# RetinaAdapterBoard.net
KiCad netlist of a schematic drawn in EAGLE
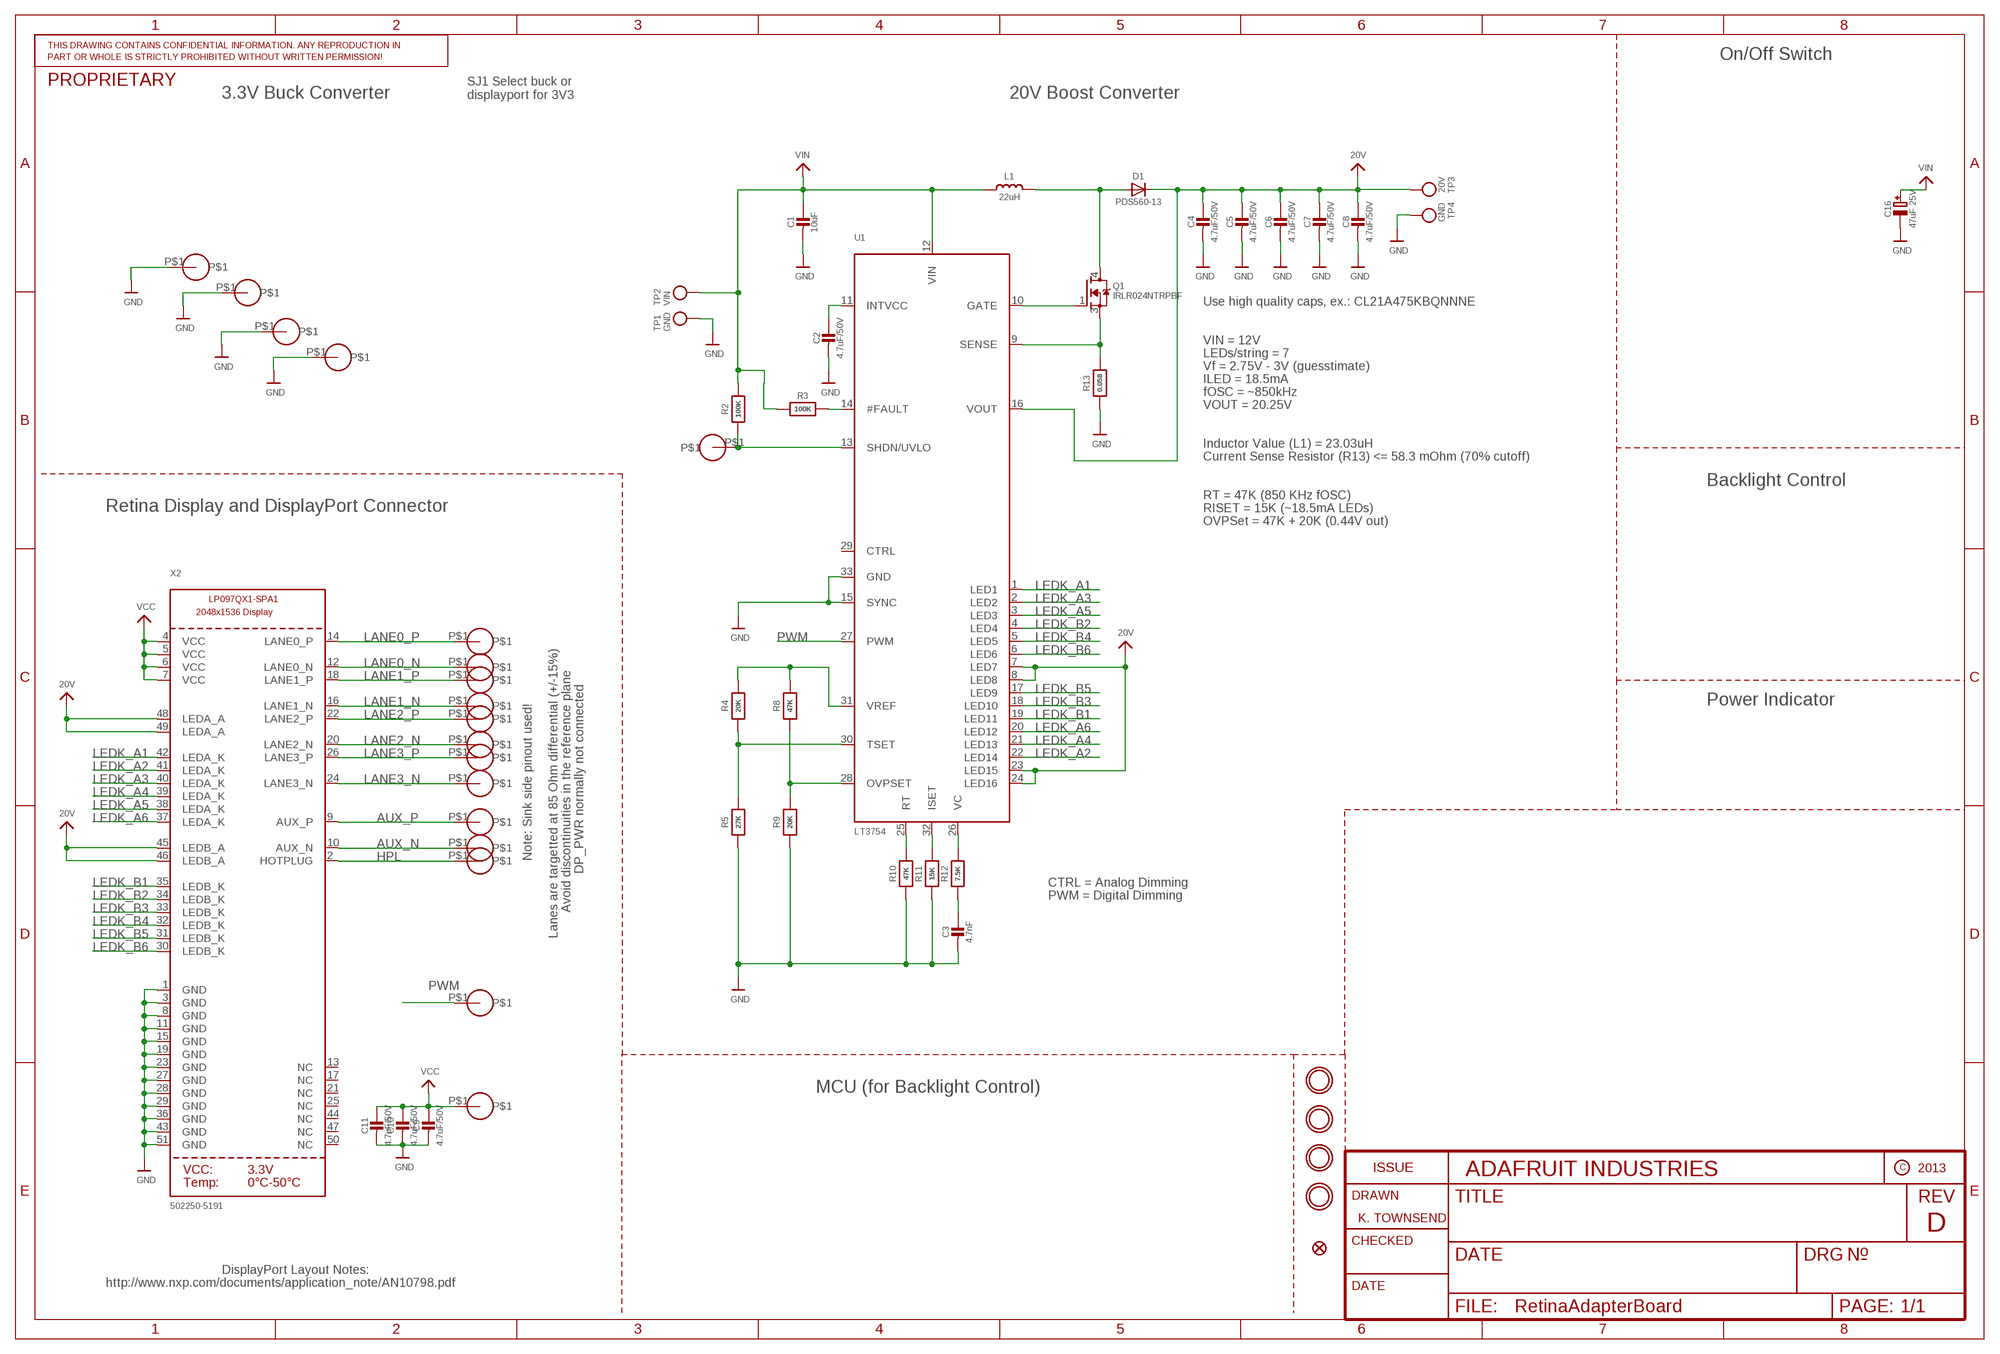
[diagram p0: schematic, sheet 1]

(export (version "E")
  (design (tool "Eeschema 10.0.6"))
  (components
    (comp (ref "C1")
      (value "10uF")
      (footprint "eagle-import:_0805")
      (libsource (lib "eagle-import") (part "CAP_CERAMIC_0805"))
    )
    (comp (ref "C2")
      (value "4.7uF/50V")
      (footprint "eagle-import:_0805")
      (libsource (lib "eagle-import") (part "CAP_CERAMIC_0805"))
    )
    (comp (ref "C3")
      (value "4.7nF")
      (footprint "eagle-import:_0805")
      (libsource (lib "eagle-import") (part "CAP_CERAMIC_0805"))
    )
    (comp (ref "C4")
      (value "4.7uF/50V")
      (footprint "eagle-import:_0805")
      (libsource (lib "eagle-import") (part "CAP_CERAMIC_0805"))
    )
    (comp (ref "C5")
      (value "4.7uF/50V")
      (footprint "eagle-import:_0805")
      (libsource (lib "eagle-import") (part "CAP_CERAMIC_0805"))
    )
    (comp (ref "C6")
      (value "4.7uF/50V")
      (footprint "eagle-import:_0805")
      (libsource (lib "eagle-import") (part "CAP_CERAMIC_0805"))
    )
    (comp (ref "C7")
      (value "4.7uF/50V")
      (footprint "eagle-import:_0805")
      (libsource (lib "eagle-import") (part "CAP_CERAMIC_0805"))
    )
    (comp (ref "C8")
      (value "4.7uF/50V")
      (footprint "eagle-import:_0805")
      (libsource (lib "eagle-import") (part "CAP_CERAMIC_0805"))
    )
    (comp (ref "C9")
      (value "4.7uF/50V")
      (footprint "eagle-import:_0805")
      (libsource (lib "eagle-import") (part "CAP_CERAMIC_0805"))
    )
    (comp (ref "C10")
      (value "4.7uF/50V")
      (footprint "eagle-import:_0805")
      (libsource (lib "eagle-import") (part "CAP_CERAMIC_0805"))
    )
    (comp (ref "C11")
      (value "4.7uF/50V")
      (footprint "eagle-import:_0805")
      (libsource (lib "eagle-import") (part "CAP_CERAMIC_0805"))
    )
    (comp (ref "C16")
      (value "47uF 25V")
      (footprint "eagle-import:PANASONIC_C")
      (libsource (lib "eagle-import") (part "CAP_ELECTROLYTICPANASONIC_C"))
    )
    (comp (ref "D1")
      (value "PDS560-13")
      (footprint "eagle-import:POWERDI-5")
      (libsource (lib "eagle-import") (part "DIODEPOWERDI"))
    )
    (comp (ref "FID3")
      (value "FIDUCIAL\"\"")
      (footprint "eagle-import:FIDUCIAL_1MM")
      (libsource (lib "eagle-import") (part "FIDUCIAL{dblquote}{dblquote}"))
    )
    (comp (ref "L1")
      (value "22uH")
      (footprint "eagle-import:INDUCTOR_6X6MM_SUMIDA_CDRH5D28")
      (libsource (lib "eagle-import") (part "INDUCTORCDRH5D28"))
    )
    (comp (ref "Q1")
      (value "IRLR024NTRPBF")
      (footprint "eagle-import:DPAK")
      (libsource (lib "eagle-import") (part "MOSFET-NDPAK"))
    )
    (comp (ref "R2")
      (value "100K")
      (footprint "eagle-import:_0805")
      (libsource (lib "eagle-import") (part "RESISTOR_0805"))
    )
    (comp (ref "R3")
      (value "100K")
      (footprint "eagle-import:_0805")
      (libsource (lib "eagle-import") (part "RESISTOR_0805"))
    )
    (comp (ref "R4")
      (value "20K")
      (footprint "eagle-import:_0805")
      (libsource (lib "eagle-import") (part "RESISTOR_0805"))
    )
    (comp (ref "R5")
      (value "27K")
      (footprint "eagle-import:_0805")
      (libsource (lib "eagle-import") (part "RESISTOR_0805"))
    )
    (comp (ref "R8")
      (value "47K")
      (footprint "eagle-import:_0805")
      (libsource (lib "eagle-import") (part "RESISTOR_0805"))
    )
    (comp (ref "R9")
      (value "20K")
      (footprint "eagle-import:_0805")
      (libsource (lib "eagle-import") (part "RESISTOR_0805"))
    )
    (comp (ref "R10")
      (value "47K")
      (footprint "eagle-import:_0805")
      (libsource (lib "eagle-import") (part "RESISTOR_0805"))
    )
    (comp (ref "R11")
      (value "15K")
      (footprint "eagle-import:_0805")
      (libsource (lib "eagle-import") (part "RESISTOR_0805"))
    )
    (comp (ref "R12")
      (value "7.5K")
      (footprint "eagle-import:_0805")
      (libsource (lib "eagle-import") (part "RESISTOR_0805"))
    )
    (comp (ref "R13")
      (value "0.058")
      (footprint "eagle-import:2512")
      (libsource (lib "eagle-import") (part "RESISTOR2512"))
    )
    (comp (ref "TP1")
      (value "GND")
      (footprint "eagle-import:TESTPOINT_ROUND_1MM")
      (libsource (lib "eagle-import") (part "TESTPOINTROUND1MM"))
    )
    (comp (ref "TP2")
      (value "VIN")
      (footprint "eagle-import:TESTPOINT_ROUND_1MM")
      (libsource (lib "eagle-import") (part "TESTPOINTROUND1MM"))
    )
    (comp (ref "TP3")
      (value "20V")
      (footprint "eagle-import:TESTPOINT_ROUND_1MM")
      (libsource (lib "eagle-import") (part "TESTPOINTROUND1MM"))
    )
    (comp (ref "TP4")
      (value "GND")
      (footprint "eagle-import:TESTPOINT_ROUND_1MM")
      (libsource (lib "eagle-import") (part "TESTPOINTROUND1MM"))
    )
    (comp (ref "U$1")
      (value "SOLDERPAD")
      (footprint "eagle-import:SOLDERPAD")
      (libsource (lib "eagle-import") (part "SOLDERPAD"))
    )
    (comp (ref "U$4")
      (value "SOLDERPAD")
      (footprint "eagle-import:SOLDERPAD")
      (libsource (lib "eagle-import") (part "SOLDERPAD"))
    )
    (comp (ref "U$9")
      (value "SOLDERPAD")
      (footprint "eagle-import:SOLDERPAD")
      (libsource (lib "eagle-import") (part "SOLDERPAD"))
    )
    (comp (ref "U$10")
      (value "SOLDERPAD")
      (footprint "eagle-import:SOLDERPAD")
      (libsource (lib "eagle-import") (part "SOLDERPAD"))
    )
    (comp (ref "U$11")
      (value "MOUNTINGHOLE3.0THIN")
      (footprint "eagle-import:MOUNTINGHOLE_3.0_PLATEDTHIN")
      (libsource (lib "eagle-import") (part "MOUNTINGHOLE3.0THIN"))
    )
    (comp (ref "U$13")
      (value "SOLDERPAD")
      (footprint "eagle-import:SOLDERPAD")
      (libsource (lib "eagle-import") (part "SOLDERPAD"))
    )
    (comp (ref "U$15")
      (value "SOLDERPAD")
      (footprint "eagle-import:SOLDERPAD")
      (libsource (lib "eagle-import") (part "SOLDERPAD"))
    )
    (comp (ref "U$32")
      (value "MOUNTINGHOLE3.0THIN")
      (footprint "eagle-import:MOUNTINGHOLE_3.0_PLATEDTHIN")
      (libsource (lib "eagle-import") (part "MOUNTINGHOLE3.0THIN"))
    )
    (comp (ref "U$33")
      (value "MOUNTINGHOLE3.0THIN")
      (footprint "eagle-import:MOUNTINGHOLE_3.0_PLATEDTHIN")
      (libsource (lib "eagle-import") (part "MOUNTINGHOLE3.0THIN"))
    )
    (comp (ref "U$34")
      (value "MOUNTINGHOLE3.0THIN")
      (footprint "eagle-import:MOUNTINGHOLE_3.0_PLATEDTHIN")
      (libsource (lib "eagle-import") (part "MOUNTINGHOLE3.0THIN"))
    )
    (comp (ref "U$43")
      (value "SOLDERPAD")
      (footprint "eagle-import:SOLDERPAD")
      (libsource (lib "eagle-import") (part "SOLDERPAD"))
    )
    (comp (ref "U$46")
      (value "SOLDERPAD")
      (footprint "eagle-import:SOLDERPAD")
      (libsource (lib "eagle-import") (part "SOLDERPAD"))
    )
    (comp (ref "U$47")
      (value "SOLDERPAD")
      (footprint "eagle-import:SOLDERPAD")
      (libsource (lib "eagle-import") (part "SOLDERPAD"))
    )
    (comp (ref "U$48")
      (value "SOLDERPAD")
      (footprint "eagle-import:SOLDERPAD")
      (libsource (lib "eagle-import") (part "SOLDERPAD"))
    )
    (comp (ref "U$49")
      (value "SOLDERPAD")
      (footprint "eagle-import:SOLDERPAD")
      (libsource (lib "eagle-import") (part "SOLDERPAD"))
    )
    (comp (ref "U$50")
      (value "SOLDERPAD")
      (footprint "eagle-import:SOLDERPAD")
      (libsource (lib "eagle-import") (part "SOLDERPAD"))
    )
    (comp (ref "U$51")
      (value "SOLDERPAD")
      (footprint "eagle-import:SOLDERPAD")
      (libsource (lib "eagle-import") (part "SOLDERPAD"))
    )
    (comp (ref "U$52")
      (value "SOLDERPAD")
      (footprint "eagle-import:SOLDERPAD")
      (libsource (lib "eagle-import") (part "SOLDERPAD"))
    )
    (comp (ref "U$53")
      (value "SOLDERPAD")
      (footprint "eagle-import:SOLDERPAD")
      (libsource (lib "eagle-import") (part "SOLDERPAD"))
    )
    (comp (ref "U$54")
      (value "SOLDERPAD")
      (footprint "eagle-import:SOLDERPAD")
      (libsource (lib "eagle-import") (part "SOLDERPAD"))
    )
    (comp (ref "U$55")
      (value "SOLDERPAD")
      (footprint "eagle-import:SOLDERPAD")
      (libsource (lib "eagle-import") (part "SOLDERPAD"))
    )
    (comp (ref "U$57")
      (value "SOLDERPAD")
      (footprint "eagle-import:SOLDERPAD")
      (libsource (lib "eagle-import") (part "SOLDERPAD"))
    )
    (comp (ref "U1")
      (value "LT3754")
      (footprint "eagle-import:QFN32_5MM")
      (libsource (lib "eagle-import") (part "VREG_LT3754"))
    )
    (comp (ref "X2")
      (value "502250-5191")
      (footprint "eagle-import:FPC_51PIN_502250-5191_EXT")
      (libsource (lib "eagle-import") (part "DISP_DISPLAYPORT_LP097QX1-SPA1HANDSOLDERING"))
    )
  )
  (nets
    (net (code "1") (name "/AUX_N") (class "Default")
      (node (ref "U$1") (pin "P$1") (pinfunction "P$1_P$1") (pintype "bidirectional"))
      (node (ref "X2") (pin "10") (pinfunction "AUX_N_10") (pintype "bidirectional"))
    )
    (net (code "2") (name "/AUX_P") (class "Default")
      (node (ref "U$43") (pin "P$1") (pinfunction "P$1_P$1") (pintype "bidirectional"))
      (node (ref "X2") (pin "9") (pinfunction "AUX_P_9") (pintype "bidirectional"))
    )
    (net (code "3") (name "/HPL") (class "Default")
      (node (ref "U$54") (pin "P$1") (pinfunction "P$1_P$1") (pintype "bidirectional"))
      (node (ref "X2") (pin "2") (pinfunction "HOTPLUG_2") (pintype "bidirectional"))
    )
    (net (code "4") (name "/LANE0_N") (class "Default")
      (node (ref "U$52") (pin "P$1") (pinfunction "P$1_P$1") (pintype "bidirectional"))
      (node (ref "X2") (pin "12") (pinfunction "LANE0_N_12") (pintype "bidirectional"))
    )
    (net (code "5") (name "/LANE0_P") (class "Default")
      (node (ref "U$53") (pin "P$1") (pinfunction "P$1_P$1") (pintype "bidirectional"))
      (node (ref "X2") (pin "14") (pinfunction "LANE0_P_14") (pintype "bidirectional"))
    )
    (net (code "6") (name "/LANE1_N") (class "Default")
      (node (ref "U$50") (pin "P$1") (pinfunction "P$1_P$1") (pintype "bidirectional"))
      (node (ref "X2") (pin "16") (pinfunction "LANE1_N_16") (pintype "bidirectional"))
    )
    (net (code "7") (name "/LANE1_P") (class "Default")
      (node (ref "U$51") (pin "P$1") (pinfunction "P$1_P$1") (pintype "bidirectional"))
      (node (ref "X2") (pin "18") (pinfunction "LANE1_P_18") (pintype "bidirectional"))
    )
    (net (code "8") (name "/LANE2_N") (class "Default")
      (node (ref "U$48") (pin "P$1") (pinfunction "P$1_P$1") (pintype "bidirectional"))
      (node (ref "X2") (pin "20") (pinfunction "LANE2_N_20") (pintype "bidirectional"))
    )
    (net (code "9") (name "/LANE2_P") (class "Default")
      (node (ref "U$49") (pin "P$1") (pinfunction "P$1_P$1") (pintype "bidirectional"))
      (node (ref "X2") (pin "22") (pinfunction "LANE2_P_22") (pintype "bidirectional"))
    )
    (net (code "10") (name "/LANE3_N") (class "Default")
      (node (ref "U$46") (pin "P$1") (pinfunction "P$1_P$1") (pintype "bidirectional"))
      (node (ref "X2") (pin "24") (pinfunction "LANE3_N_24") (pintype "bidirectional"))
    )
    (net (code "11") (name "/LANE3_P") (class "Default")
      (node (ref "U$47") (pin "P$1") (pinfunction "P$1_P$1") (pintype "bidirectional"))
      (node (ref "X2") (pin "26") (pinfunction "LANE3_P_26") (pintype "bidirectional"))
    )
    (net (code "12") (name "/LEDK_A1") (class "Default")
      (node (ref "U1") (pin "1") (pinfunction "LED1_1") (pintype "bidirectional"))
      (node (ref "X2") (pin "42") (pinfunction "LEDA_K_42") (pintype "bidirectional"))
    )
    (net (code "13") (name "/LEDK_A2") (class "Default")
      (node (ref "U1") (pin "22") (pinfunction "LED14_22") (pintype "bidirectional"))
      (node (ref "X2") (pin "41") (pinfunction "LEDA_K_41") (pintype "bidirectional"))
    )
    (net (code "14") (name "/LEDK_A3") (class "Default")
      (node (ref "U1") (pin "2") (pinfunction "LED2_2") (pintype "bidirectional"))
      (node (ref "X2") (pin "40") (pinfunction "LEDA_K_40") (pintype "bidirectional"))
    )
    (net (code "15") (name "/LEDK_A4") (class "Default")
      (node (ref "U1") (pin "21") (pinfunction "LED13_21") (pintype "bidirectional"))
      (node (ref "X2") (pin "39") (pinfunction "LEDA_K_39") (pintype "bidirectional"))
    )
    (net (code "16") (name "/LEDK_A5") (class "Default")
      (node (ref "U1") (pin "3") (pinfunction "LED3_3") (pintype "bidirectional"))
      (node (ref "X2") (pin "38") (pinfunction "LEDA_K_38") (pintype "bidirectional"))
    )
    (net (code "17") (name "/LEDK_A6") (class "Default")
      (node (ref "U1") (pin "20") (pinfunction "LED12_20") (pintype "bidirectional"))
      (node (ref "X2") (pin "37") (pinfunction "LEDA_K_37") (pintype "bidirectional"))
    )
    (net (code "18") (name "/LEDK_B1") (class "Default")
      (node (ref "U1") (pin "19") (pinfunction "LED11_19") (pintype "bidirectional"))
      (node (ref "X2") (pin "35") (pinfunction "LEDB_K_35") (pintype "bidirectional"))
    )
    (net (code "19") (name "/LEDK_B2") (class "Default")
      (node (ref "U1") (pin "4") (pinfunction "LED4_4") (pintype "bidirectional"))
      (node (ref "X2") (pin "34") (pinfunction "LEDB_K_34") (pintype "bidirectional"))
    )
    (net (code "20") (name "/LEDK_B3") (class "Default")
      (node (ref "U1") (pin "18") (pinfunction "LED10_18") (pintype "bidirectional"))
      (node (ref "X2") (pin "33") (pinfunction "LEDB_K_33") (pintype "bidirectional"))
    )
    (net (code "21") (name "/LEDK_B4") (class "Default")
      (node (ref "U1") (pin "5") (pinfunction "LED5_5") (pintype "bidirectional"))
      (node (ref "X2") (pin "32") (pinfunction "LEDB_K_32") (pintype "bidirectional"))
    )
    (net (code "22") (name "/LEDK_B5") (class "Default")
      (node (ref "U1") (pin "17") (pinfunction "LED9_17") (pintype "bidirectional"))
      (node (ref "X2") (pin "31") (pinfunction "LEDB_K_31") (pintype "bidirectional"))
    )
    (net (code "23") (name "/LEDK_B6") (class "Default")
      (node (ref "U1") (pin "6") (pinfunction "LED6_6") (pintype "bidirectional"))
      (node (ref "X2") (pin "30") (pinfunction "LEDB_K_30") (pintype "bidirectional"))
    )
    (net (code "24") (name "/PWM") (class "Default")
      (node (ref "U$57") (pin "P$1") (pinfunction "P$1_P$1") (pintype "bidirectional"))
      (node (ref "U1") (pin "27") (pinfunction "PWM_27") (pintype "bidirectional"))
    )
    (net (code "25") (name "20V") (class "Default")
      (node (ref "C4") (pin "1") (pinfunction "1_1") (pintype "passive"))
      (node (ref "C5") (pin "1") (pinfunction "1_1") (pintype "passive"))
      (node (ref "C6") (pin "1") (pinfunction "1_1") (pintype "passive"))
      (node (ref "C7") (pin "1") (pinfunction "1_1") (pintype "passive"))
      (node (ref "C8") (pin "1") (pinfunction "1_1") (pintype "passive"))
      (node (ref "D1") (pin "C") (pinfunction "C_C") (pintype "passive"))
      (node (ref "TP3") (pin "P$1") (pinfunction "P$1_P$1") (pintype "bidirectional"))
      (node (ref "U1") (pin "16") (pinfunction "VOUT_16") (pintype "bidirectional"))
      (node (ref "U1") (pin "23") (pinfunction "LED15_23") (pintype "bidirectional"))
      (node (ref "U1") (pin "24") (pinfunction "LED16_24") (pintype "bidirectional"))
      (node (ref "U1") (pin "7") (pinfunction "LED7_7") (pintype "bidirectional"))
      (node (ref "U1") (pin "8") (pinfunction "LED8_8") (pintype "bidirectional"))
      (node (ref "X2") (pin "45") (pinfunction "LEDB_A_45") (pintype "bidirectional"))
      (node (ref "X2") (pin "46") (pinfunction "LEDB_A_46") (pintype "bidirectional"))
      (node (ref "X2") (pin "48") (pinfunction "LEDA_A_48") (pintype "bidirectional"))
      (node (ref "X2") (pin "49") (pinfunction "LEDA_A_49") (pintype "bidirectional"))
    )
    (net (code "26") (name "GND") (class "Default")
      (node (ref "C1") (pin "2") (pinfunction "2_2") (pintype "passive"))
      (node (ref "C10") (pin "2") (pinfunction "2_2") (pintype "passive"))
      (node (ref "C11") (pin "2") (pinfunction "2_2") (pintype "passive"))
      (node (ref "C16") (pin "-") (pinfunction "-_-") (pintype "passive"))
      (node (ref "C2") (pin "2") (pinfunction "2_2") (pintype "passive"))
      (node (ref "C3") (pin "2") (pinfunction "2_2") (pintype "passive"))
      (node (ref "C4") (pin "2") (pinfunction "2_2") (pintype "passive"))
      (node (ref "C5") (pin "2") (pinfunction "2_2") (pintype "passive"))
      (node (ref "C6") (pin "2") (pinfunction "2_2") (pintype "passive"))
      (node (ref "C7") (pin "2") (pinfunction "2_2") (pintype "passive"))
      (node (ref "C8") (pin "2") (pinfunction "2_2") (pintype "passive"))
      (node (ref "C9") (pin "2") (pinfunction "2_2") (pintype "passive"))
      (node (ref "R10") (pin "1") (pinfunction "1_1") (pintype "passive"))
      (node (ref "R11") (pin "1") (pinfunction "1_1") (pintype "passive"))
      (node (ref "R13") (pin "1") (pinfunction "1_1") (pintype "passive"))
      (node (ref "R5") (pin "1") (pinfunction "1_1") (pintype "passive"))
      (node (ref "R9") (pin "1") (pinfunction "1_1") (pintype "passive"))
      (node (ref "TP1") (pin "P$1") (pinfunction "P$1_P$1") (pintype "bidirectional"))
      (node (ref "TP4") (pin "P$1") (pinfunction "P$1_P$1") (pintype "bidirectional"))
      (node (ref "U$10") (pin "P$1") (pinfunction "P$1_P$1") (pintype "bidirectional"))
      (node (ref "U$13") (pin "P$1") (pinfunction "P$1_P$1") (pintype "bidirectional"))
      (node (ref "U$15") (pin "P$1") (pinfunction "P$1_P$1") (pintype "bidirectional"))
      (node (ref "U$55") (pin "P$1") (pinfunction "P$1_P$1") (pintype "bidirectional"))
      (node (ref "U1") (pin "15") (pinfunction "SYNC_15") (pintype "bidirectional"))
      (node (ref "U1") (pin "33") (pinfunction "GND_33") (pintype "bidirectional"))
      (node (ref "X2") (pin "1") (pinfunction "GND_1") (pintype "power_in"))
      (node (ref "X2") (pin "11") (pinfunction "GND_11") (pintype "power_in"))
      (node (ref "X2") (pin "15") (pinfunction "GND_15") (pintype "power_in"))
      (node (ref "X2") (pin "19") (pinfunction "GND_19") (pintype "power_in"))
      (node (ref "X2") (pin "23") (pinfunction "GND_23") (pintype "power_in"))
      (node (ref "X2") (pin "27") (pinfunction "GND_27") (pintype "power_in"))
      (node (ref "X2") (pin "28") (pinfunction "GND_28") (pintype "power_in"))
      (node (ref "X2") (pin "29") (pinfunction "GND_29") (pintype "power_in"))
      (node (ref "X2") (pin "3") (pinfunction "GND_3") (pintype "power_in"))
      (node (ref "X2") (pin "36") (pinfunction "GND_36") (pintype "power_in"))
      (node (ref "X2") (pin "43") (pinfunction "GND_43") (pintype "power_in"))
      (node (ref "X2") (pin "51") (pinfunction "GND_51") (pintype "power_in"))
      (node (ref "X2") (pin "8") (pinfunction "GND_8") (pintype "power_in"))
    )
    (net (code "27") (name "Net-(C3-Pad1)") (class "Default")
      (node (ref "C3") (pin "1") (pinfunction "1_1") (pintype "passive"))
      (node (ref "R12") (pin "1") (pinfunction "1_1") (pintype "passive"))
    )
    (net (code "28") (name "Net-(L1-2)") (class "Default")
      (node (ref "D1") (pin "A1") (pinfunction "A_A1") (pintype "passive"))
      (node (ref "D1") (pin "A2") (pinfunction "A_A2") (pintype "passive"))
      (node (ref "L1") (pin "P$2") (pinfunction "2_P$2") (pintype "passive"))
      (node (ref "Q1") (pin "4") (pinfunction "D_4") (pintype "bidirectional"))
    )
    (net (code "29") (name "Net-(Q1-G)") (class "Default")
      (node (ref "Q1") (pin "1") (pinfunction "G_1") (pintype "bidirectional"))
      (node (ref "U1") (pin "10") (pinfunction "GATE_10") (pintype "bidirectional"))
    )
    (net (code "30") (name "Net-(Q1-S)") (class "Default")
      (node (ref "Q1") (pin "3") (pinfunction "S_3") (pintype "bidirectional"))
      (node (ref "R13") (pin "2") (pinfunction "2_2") (pintype "passive"))
      (node (ref "U1") (pin "9") (pinfunction "SENSE_9") (pintype "bidirectional"))
    )
    (net (code "31") (name "Net-(U1-#FAULT)") (class "Default")
      (node (ref "R3") (pin "2") (pinfunction "2_2") (pintype "passive"))
      (node (ref "U1") (pin "14") (pinfunction "#FAULT_14") (pintype "bidirectional"))
    )
    (net (code "32") (name "Net-(U1-INTVCC)") (class "Default")
      (node (ref "C2") (pin "1") (pinfunction "1_1") (pintype "passive"))
      (node (ref "U1") (pin "11") (pinfunction "INTVCC_11") (pintype "bidirectional"))
    )
    (net (code "33") (name "Net-(U1-ISET)") (class "Default")
      (node (ref "R11") (pin "2") (pinfunction "2_2") (pintype "passive"))
      (node (ref "U1") (pin "32") (pinfunction "ISET_32") (pintype "bidirectional"))
    )
    (net (code "34") (name "Net-(U1-OVPSET)") (class "Default")
      (node (ref "R8") (pin "1") (pinfunction "1_1") (pintype "passive"))
      (node (ref "R9") (pin "2") (pinfunction "2_2") (pintype "passive"))
      (node (ref "U1") (pin "28") (pinfunction "OVPSET_28") (pintype "bidirectional"))
    )
    (net (code "35") (name "Net-(U1-RT)") (class "Default")
      (node (ref "R10") (pin "2") (pinfunction "2_2") (pintype "passive"))
      (node (ref "U1") (pin "25") (pinfunction "RT_25") (pintype "bidirectional"))
    )
    (net (code "36") (name "Net-(U1-SHDN{slash}UVLO)") (class "Default")
      (node (ref "R2") (pin "1") (pinfunction "1_1") (pintype "passive"))
      (node (ref "U$9") (pin "P$1") (pinfunction "P$1_P$1") (pintype "bidirectional"))
      (node (ref "U1") (pin "13") (pinfunction "SHDN/UVLO_13") (pintype "bidirectional"))
    )
    (net (code "37") (name "Net-(U1-TSET)") (class "Default")
      (node (ref "R4") (pin "1") (pinfunction "1_1") (pintype "passive"))
      (node (ref "R5") (pin "2") (pinfunction "2_2") (pintype "passive"))
      (node (ref "U1") (pin "30") (pinfunction "TSET_30") (pintype "bidirectional"))
    )
    (net (code "38") (name "Net-(U1-VC)") (class "Default")
      (node (ref "R12") (pin "2") (pinfunction "2_2") (pintype "passive"))
      (node (ref "U1") (pin "26") (pinfunction "VC_26") (pintype "bidirectional"))
    )
    (net (code "39") (name "Net-(U1-VREF)") (class "Default")
      (node (ref "R4") (pin "2") (pinfunction "2_2") (pintype "passive"))
      (node (ref "R8") (pin "2") (pinfunction "2_2") (pintype "passive"))
      (node (ref "U1") (pin "31") (pinfunction "VREF_31") (pintype "bidirectional"))
    )
    (net (code "40") (name "VCC") (class "Default")
      (node (ref "C10") (pin "1") (pinfunction "1_1") (pintype "passive"))
      (node (ref "C11") (pin "1") (pinfunction "1_1") (pintype "passive"))
      (node (ref "C9") (pin "1") (pinfunction "1_1") (pintype "passive"))
      (node (ref "U$4") (pin "P$1") (pinfunction "P$1_P$1") (pintype "bidirectional"))
      (node (ref "X2") (pin "4") (pinfunction "VCC_4") (pintype "power_in"))
      (node (ref "X2") (pin "5") (pinfunction "VCC_5") (pintype "power_in"))
      (node (ref "X2") (pin "6") (pinfunction "VCC_6") (pintype "power_in"))
      (node (ref "X2") (pin "7") (pinfunction "VCC_7") (pintype "power_in"))
    )
    (net (code "41") (name "VIN") (class "Default")
      (node (ref "C1") (pin "1") (pinfunction "1_1") (pintype "passive"))
      (node (ref "C16") (pin "+") (pinfunction "+_+") (pintype "passive"))
      (node (ref "L1") (pin "P$1") (pinfunction "1_P$1") (pintype "passive"))
      (node (ref "R2") (pin "2") (pinfunction "2_2") (pintype "passive"))
      (node (ref "R3") (pin "1") (pinfunction "1_1") (pintype "passive"))
      (node (ref "TP2") (pin "P$1") (pinfunction "P$1_P$1") (pintype "bidirectional"))
      (node (ref "U1") (pin "12") (pinfunction "VIN_12") (pintype "bidirectional"))
    )
    (net (code "42") (name "unconnected-(U1-CTRL-Pad29)") (class "Default")
      (node (ref "U1") (pin "29") (pinfunction "CTRL_29") (pintype "bidirectional"))
    )
    (net (code "43") (name "unconnected-(X2-NC-Pad13)") (class "Default")
      (node (ref "X2") (pin "13") (pinfunction "NC_13") (pintype "no_connect"))
    )
    (net (code "44") (name "unconnected-(X2-NC-Pad17)") (class "Default")
      (node (ref "X2") (pin "17") (pinfunction "NC_17") (pintype "no_connect"))
    )
    (net (code "45") (name "unconnected-(X2-NC-Pad21)") (class "Default")
      (node (ref "X2") (pin "21") (pinfunction "NC_21") (pintype "no_connect"))
    )
    (net (code "46") (name "unconnected-(X2-NC-Pad25)") (class "Default")
      (node (ref "X2") (pin "25") (pinfunction "NC_25") (pintype "no_connect"))
    )
    (net (code "47") (name "unconnected-(X2-NC-Pad44)") (class "Default")
      (node (ref "X2") (pin "44") (pinfunction "NC_44") (pintype "no_connect"))
    )
    (net (code "48") (name "unconnected-(X2-NC-Pad47)") (class "Default")
      (node (ref "X2") (pin "47") (pinfunction "NC_47") (pintype "no_connect"))
    )
    (net (code "49") (name "unconnected-(X2-NC-Pad50)") (class "Default")
      (node (ref "X2") (pin "50") (pinfunction "NC_50") (pintype "no_connect"))
    )
  )
)
